# tomada_esp-tom.net
KiCad netlist of a schematic drawn in EAGLE
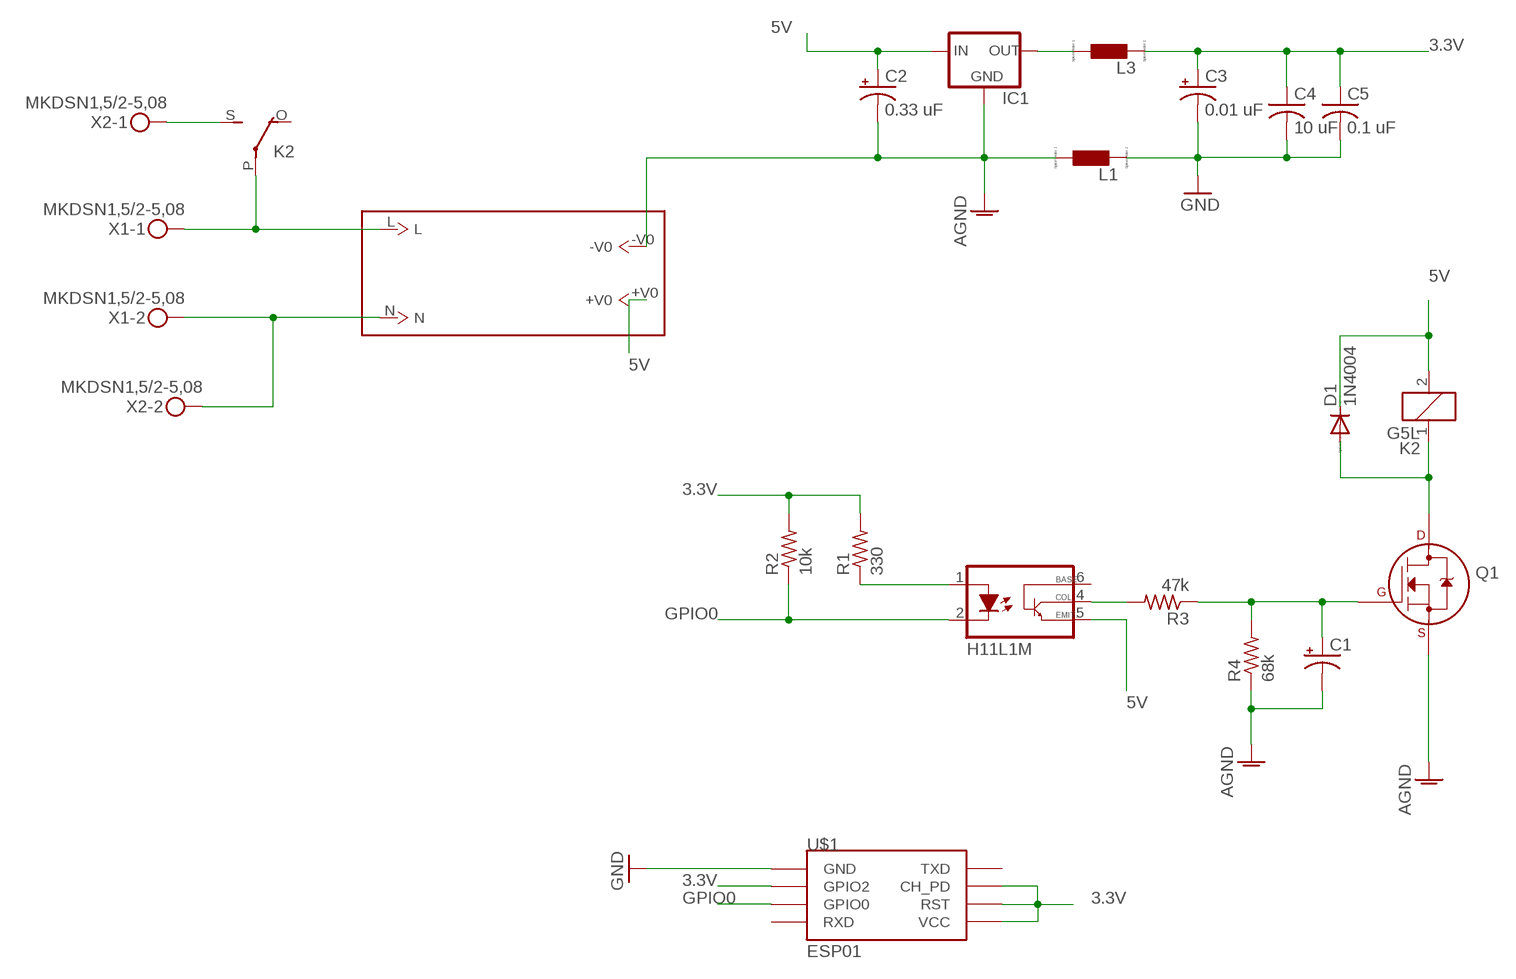
[diagram p0: schematic, sheet 1]

(export (version "E")
  (design (tool "Eeschema 10.0.6"))
  (components
    (comp (ref "C1")
      (value "CPOL-USE2-5")
      (footprint "eagle-import:E2-5")
      (libsource (lib "eagle-import") (part "CPOL-USE2-5"))
    )
    (comp (ref "C2")
      (value "0.33 uF")
      (footprint "eagle-import:E2-5")
      (libsource (lib "eagle-import") (part "CPOL-USE2-5"))
    )
    (comp (ref "C3")
      (value "0.01 uF")
      (footprint "eagle-import:E2-5")
      (libsource (lib "eagle-import") (part "CPOL-USE2-5"))
    )
    (comp (ref "C4")
      (value "10 uF")
      (footprint "eagle-import:C025-024X044")
      (libsource (lib "eagle-import") (part "C-US025-024X044"))
    )
    (comp (ref "C5")
      (value "0.1 uF")
      (footprint "eagle-import:C025-024X044")
      (libsource (lib "eagle-import") (part "C-US025-024X044"))
    )
    (comp (ref "D1")
      (value "1N4004")
      (footprint "eagle-import:DO41-10")
      (libsource (lib "eagle-import") (part "1N4004"))
    )
    (comp (ref "IC1")
      (value "78LXX")
      (footprint "eagle-import:78LXX")
      (libsource (lib "eagle-import") (part "78LXX"))
    )
    (comp (ref "K2")
      (value "G5L")
      (footprint "eagle-import:G5LE")
      (libsource (lib "eagle-import") (part "G5L"))
    )
    (comp (ref "L1")
      (value "L0207/10")
      (footprint "eagle-import:0207_10")
      (libsource (lib "eagle-import") (part "L0207/10"))
    )
    (comp (ref "L3")
      (value "L0207/10")
      (footprint "eagle-import:0207_10")
      (libsource (lib "eagle-import") (part "L0207/10"))
    )
    (comp (ref "OK1")
      (value "H11L1M")
      (footprint "eagle-import:DIL06")
      (fields (field (name "MF") "FAIRCHILD SEMICONDUCTOR") (field (name "MPN") "H11L1-M"))
      (libsource (lib "eagle-import") (part "H11LM1"))
    )
    (comp (ref "Q1")
      (value "2N7000_TO92")
      (footprint "eagle-import:TO-92")
      (libsource (lib "eagle-import") (part "2N700_TO920"))
    )
    (comp (ref "R1")
      (value "330")
      (footprint "eagle-import:0204_7")
      (libsource (lib "eagle-import") (part "R-US_0204/7"))
    )
    (comp (ref "R2")
      (value "10k")
      (footprint "eagle-import:0204_7")
      (libsource (lib "eagle-import") (part "R-US_0204/7"))
    )
    (comp (ref "R3")
      (value "47k")
      (footprint "eagle-import:0204_7")
      (libsource (lib "eagle-import") (part "R-US_0204/7"))
    )
    (comp (ref "R4")
      (value "68k")
      (footprint "eagle-import:0204_7")
      (libsource (lib "eagle-import") (part "R-US_0204/7"))
    )
    (comp (ref "U$1")
      (value "ESP01")
      (footprint "eagle-import:ESP01")
      (libsource (lib "eagle-import") (part "ESP01"))
    )
    (comp (ref "U$2")
      (value "NA03-T2S05")
      (footprint "eagle-import:NA03-T2S05")
      (libsource (lib "eagle-import") (part "NA03-T2S05"))
    )
    (comp (ref "X1")
      (value "MKDSN1,5/2-5,08")
      (footprint "eagle-import:MKDSN1,5_2-5,08")
      (libsource (lib "eagle-import") (part "MKDSN1,5/2-5,08"))
    )
    (comp (ref "X2")
      (value "MKDSN1,5/2-5,08")
      (footprint "eagle-import:MKDSN1,5_2-5,08")
      (libsource (lib "eagle-import") (part "MKDSN1,5/2-5,08"))
    )
  )
  (nets
    (net (code "1") (name "/3.3V") (class "Default")
      (node (ref "C3") (pin "+") (pinfunction "+_+") (pintype "passive"))
      (node (ref "C4") (pin "1") (pinfunction "1_1") (pintype "passive"))
      (node (ref "C5") (pin "1") (pinfunction "1_1") (pintype "passive"))
      (node (ref "L3") (pin "2") (pinfunction "2_2") (pintype "passive"))
      (node (ref "R1") (pin "2") (pinfunction "2_2") (pintype "passive"))
      (node (ref "R2") (pin "2") (pinfunction "2_2") (pintype "passive"))
      (node (ref "U$1") (pin "CH_PD") (pinfunction "CH_PD_CH_PD") (pintype "bidirectional"))
      (node (ref "U$1") (pin "GPIO2") (pinfunction "GPIO2_GPIO2") (pintype "bidirectional"))
      (node (ref "U$1") (pin "RST") (pinfunction "RST_RST") (pintype "bidirectional"))
      (node (ref "U$1") (pin "VCC") (pinfunction "VCC_VCC") (pintype "bidirectional"))
    )
    (net (code "2") (name "/5V") (class "Default")
      (node (ref "C2") (pin "+") (pinfunction "+_+") (pintype "passive"))
      (node (ref "D1") (pin "C") (pinfunction "C_C") (pintype "passive"))
      (node (ref "IC1") (pin "IN") (pinfunction "IN_IN") (pintype "input"))
      (node (ref "K2") (pin "2") (pinfunction "2_2") (pintype "passive"))
      (node (ref "OK1") (pin "5") (pinfunction "GND_5") (pintype "power_in"))
      (node (ref "U$2") (pin "+V0") (pinfunction "+V0_+V0") (pintype "bidirectional"))
    )
    (net (code "3") (name "/GPIO0") (class "Default")
      (node (ref "OK1") (pin "2") (pinfunction "C_2") (pintype "passive"))
      (node (ref "R2") (pin "1") (pinfunction "1_1") (pintype "passive"))
      (node (ref "U$1") (pin "GPIO0") (pinfunction "GPIO0_GPIO0") (pintype "bidirectional"))
    )
    (net (code "4") (name "/VCC") (class "Default")
      (node (ref "OK1") (pin "6") (pinfunction "VCC_6") (pintype "power_in"))
    )
    (net (code "5") (name "AGND") (class "Default")
      (node (ref "C1") (pin "-") (pinfunction "-_-") (pintype "passive"))
      (node (ref "C2") (pin "-") (pinfunction "-_-") (pintype "passive"))
      (node (ref "IC1") (pin "GND") (pinfunction "GND_GND") (pintype "input"))
      (node (ref "L1") (pin "1") (pinfunction "1_1") (pintype "passive"))
      (node (ref "Q1") (pin "1") (pinfunction "S_1") (pintype "bidirectional"))
      (node (ref "R4") (pin "1") (pinfunction "1_1") (pintype "passive"))
      (node (ref "U$2") (pin "-V0") (pinfunction "-V0_-V0") (pintype "bidirectional"))
    )
    (net (code "6") (name "GND") (class "Default")
      (node (ref "C3") (pin "-") (pinfunction "-_-") (pintype "passive"))
      (node (ref "C4") (pin "2") (pinfunction "2_2") (pintype "passive"))
      (node (ref "C5") (pin "2") (pinfunction "2_2") (pintype "passive"))
      (node (ref "L1") (pin "2") (pinfunction "2_2") (pintype "passive"))
      (node (ref "U$1") (pin "GND") (pinfunction "GND_GND") (pintype "bidirectional"))
    )
    (net (code "7") (name "Net-(IC1-PadOUT)") (class "Default")
      (node (ref "IC1") (pin "OUT") (pinfunction "OUT_OUT") (pintype "passive"))
      (node (ref "L3") (pin "1") (pinfunction "1_1") (pintype "passive"))
    )
    (net (code "8") (name "Net-(OK1-A)") (class "Default")
      (node (ref "OK1") (pin "1") (pinfunction "A_1") (pintype "passive"))
      (node (ref "R1") (pin "1") (pinfunction "1_1") (pintype "passive"))
    )
    (net (code "9") (name "Net-(OK1-OUT)") (class "Default")
      (node (ref "OK1") (pin "4") (pinfunction "OUT_4") (pintype "output"))
      (node (ref "R3") (pin "2") (pinfunction "2_2") (pintype "passive"))
    )
    (net (code "10") (name "Net-(Q1-D)") (class "Default")
      (node (ref "D1") (pin "A") (pinfunction "A_A") (pintype "passive"))
      (node (ref "K2") (pin "1") (pinfunction "1_1") (pintype "passive"))
      (node (ref "Q1") (pin "3") (pinfunction "D_3") (pintype "bidirectional"))
    )
    (net (code "11") (name "Net-(Q1-G)") (class "Default")
      (node (ref "C1") (pin "+") (pinfunction "+_+") (pintype "passive"))
      (node (ref "Q1") (pin "2") (pinfunction "G_2") (pintype "tri_state"))
      (node (ref "R3") (pin "1") (pinfunction "1_1") (pintype "passive"))
      (node (ref "R4") (pin "2") (pinfunction "2_2") (pintype "passive"))
    )
    (net (code "12") (name "Net-(X1A-KL)") (class "Default")
      (node (ref "K2") (pin "P") (pinfunction "P_P") (pintype "passive"))
      (node (ref "U$2") (pin "L") (pinfunction "L_L") (pintype "bidirectional"))
      (node (ref "X1") (pin "1") (pinfunction "KL_1") (pintype "passive"))
    )
    (net (code "13") (name "Net-(X1B-KL)") (class "Default")
      (node (ref "U$2") (pin "N") (pinfunction "N_N") (pintype "bidirectional"))
      (node (ref "X1") (pin "2") (pinfunction "KL_2") (pintype "passive"))
      (node (ref "X2") (pin "2") (pinfunction "KL_2") (pintype "passive"))
    )
    (net (code "14") (name "Net-(X2A-KL)") (class "Default")
      (node (ref "K2") (pin "S") (pinfunction "S_S") (pintype "passive"))
      (node (ref "X2") (pin "1") (pinfunction "KL_1") (pintype "passive"))
    )
    (net (code "15") (name "unconnected-(K2-PadO)") (class "Default")
      (node (ref "K2") (pin "O") (pinfunction "O_O") (pintype "passive"))
    )
    (net (code "16") (name "unconnected-(U$1-RXD-PadRX)") (class "Default")
      (node (ref "U$1") (pin "RX") (pinfunction "RXD_RX") (pintype "bidirectional"))
    )
    (net (code "17") (name "unconnected-(U$1-TXD-PadTX)") (class "Default")
      (node (ref "U$1") (pin "TX") (pinfunction "TXD_TX") (pintype "bidirectional"))
    )
  )
)
